# current-monitor.net
KiCad netlist of a schematic drawn in Altium Designer
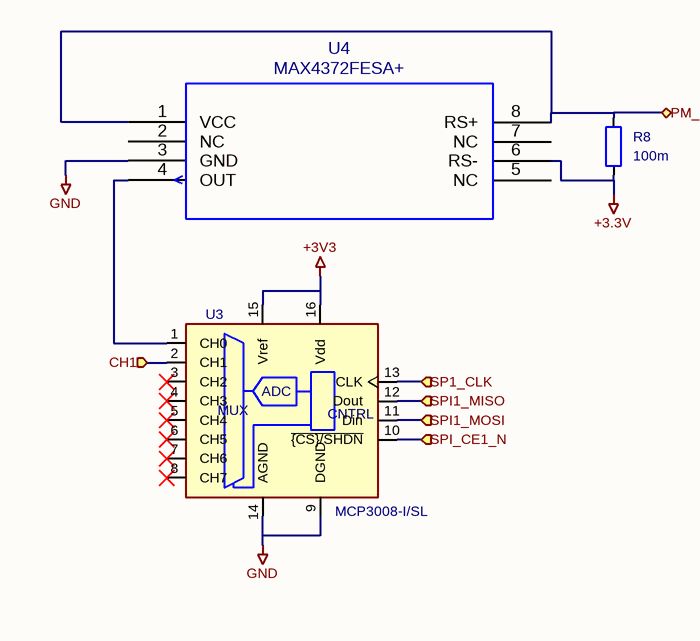
[diagram p0: current-monitor.SchDoc]

(export (version "E")
  (design (tool "Eeschema 10.0.6"))
  (components
    (comp (ref "R8") (value "100m") (libsource (lib "Device") (part "R")))
    (comp (ref "U3") (value "MCP3008-I/SL") (libsource (lib "Analog_ADC") (part "MCP3008")))
    (comp (ref "U4")
      (value "MAX4372FESA+")
      (libsource (lib "STM32_Breakout-rescue") (part "MAX4372FESA+-MAX4372FESA+"))
    )
  )
  (nets
    (net (code "1") (name "+3.3V") (class "Default")
      (node (ref "R8") (pin "2") (pinfunction "2_2") (pintype "passive"))
      (node (ref "U4") (pin "6") (pinfunction "RS-_6") (pintype "passive"))
    )
    (net (code "2") (name "+3V3") (class "Default")
      (node (ref "U3") (pin "15") (pinfunction "Vref_15") (pintype "passive"))
      (node (ref "U3") (pin "16") (pinfunction "Vdd_16") (pintype "passive"))
    )
    (net (code "3") (name "/CH1") (class "Default")
      (node (ref "U3") (pin "2") (pinfunction "CH1_2") (pintype "passive"))
    )
    (net (code "4") (name "/PM_Input") (class "Default")
      (node (ref "R8") (pin "1") (pinfunction "1_1") (pintype "passive"))
      (node (ref "U4") (pin "1") (pinfunction "VCC_1") (pintype "passive"))
      (node (ref "U4") (pin "8") (pinfunction "RS+_8") (pintype "passive"))
    )
    (net (code "5") (name "/SP1_CLK") (class "Default")
      (node (ref "U3") (pin "13") (pinfunction "CLK_13") (pintype "passive"))
    )
    (net (code "6") (name "/SPI1_MISO") (class "Default")
      (node (ref "U3") (pin "12") (pinfunction "Dout_12") (pintype "passive"))
    )
    (net (code "7") (name "/SPI1_MOSI") (class "Default")
      (node (ref "U3") (pin "11") (pinfunction "Din_11") (pintype "passive"))
    )
    (net (code "8") (name "/SPI_CE1_N") (class "Default")
      (node (ref "U3") (pin "10") (pinfunction "~{{CS}/SHDN}_10") (pintype "passive"))
    )
    (net (code "9") (name "GND") (class "Default")
      (node (ref "U3") (pin "14") (pinfunction "AGND_14") (pintype "passive"))
      (node (ref "U3") (pin "9") (pinfunction "DGND_9") (pintype "passive"))
      (node (ref "U4") (pin "3") (pinfunction "GND_3") (pintype "passive"))
    )
    (net (code "10") (name "Net-(U3-CH0)") (class "Default")
      (node (ref "U3") (pin "1") (pinfunction "CH0_1") (pintype "passive"))
      (node (ref "U4") (pin "4") (pinfunction "OUT_4") (pintype "passive"))
    )
    (net (code "11") (name "unconnected-(U3-CH2-Pad3)") (class "Default")
      (node (ref "U3") (pin "3") (pinfunction "CH2_3") (pintype "passive+no_connect"))
    )
    (net (code "12") (name "unconnected-(U3-CH3-Pad4)") (class "Default")
      (node (ref "U3") (pin "4") (pinfunction "CH3_4") (pintype "passive+no_connect"))
    )
    (net (code "13") (name "unconnected-(U3-CH4-Pad5)") (class "Default")
      (node (ref "U3") (pin "5") (pinfunction "CH4_5") (pintype "passive+no_connect"))
    )
    (net (code "14") (name "unconnected-(U3-CH5-Pad6)") (class "Default")
      (node (ref "U3") (pin "6") (pinfunction "CH5_6") (pintype "passive+no_connect"))
    )
    (net (code "15") (name "unconnected-(U3-CH6-Pad7)") (class "Default")
      (node (ref "U3") (pin "7") (pinfunction "CH6_7") (pintype "passive+no_connect"))
    )
    (net (code "16") (name "unconnected-(U3-CH7-Pad8)") (class "Default")
      (node (ref "U3") (pin "8") (pinfunction "CH7_8") (pintype "passive+no_connect"))
    )
    (net (code "17") (name "unconnected-(U4-NC-Pad2)") (class "Default")
      (node (ref "U4") (pin "2") (pinfunction "NC_2") (pintype "passive"))
    )
    (net (code "18") (name "unconnected-(U4-NC-Pad5)") (class "Default")
      (node (ref "U4") (pin "5") (pinfunction "NC_5") (pintype "passive"))
    )
    (net (code "19") (name "unconnected-(U4-NC-Pad7)") (class "Default")
      (node (ref "U4") (pin "7") (pinfunction "NC_7") (pintype "passive"))
    )
  )
)
